# chip-arduino.net
KiCad netlist of a schematic drawn in Altium Designer
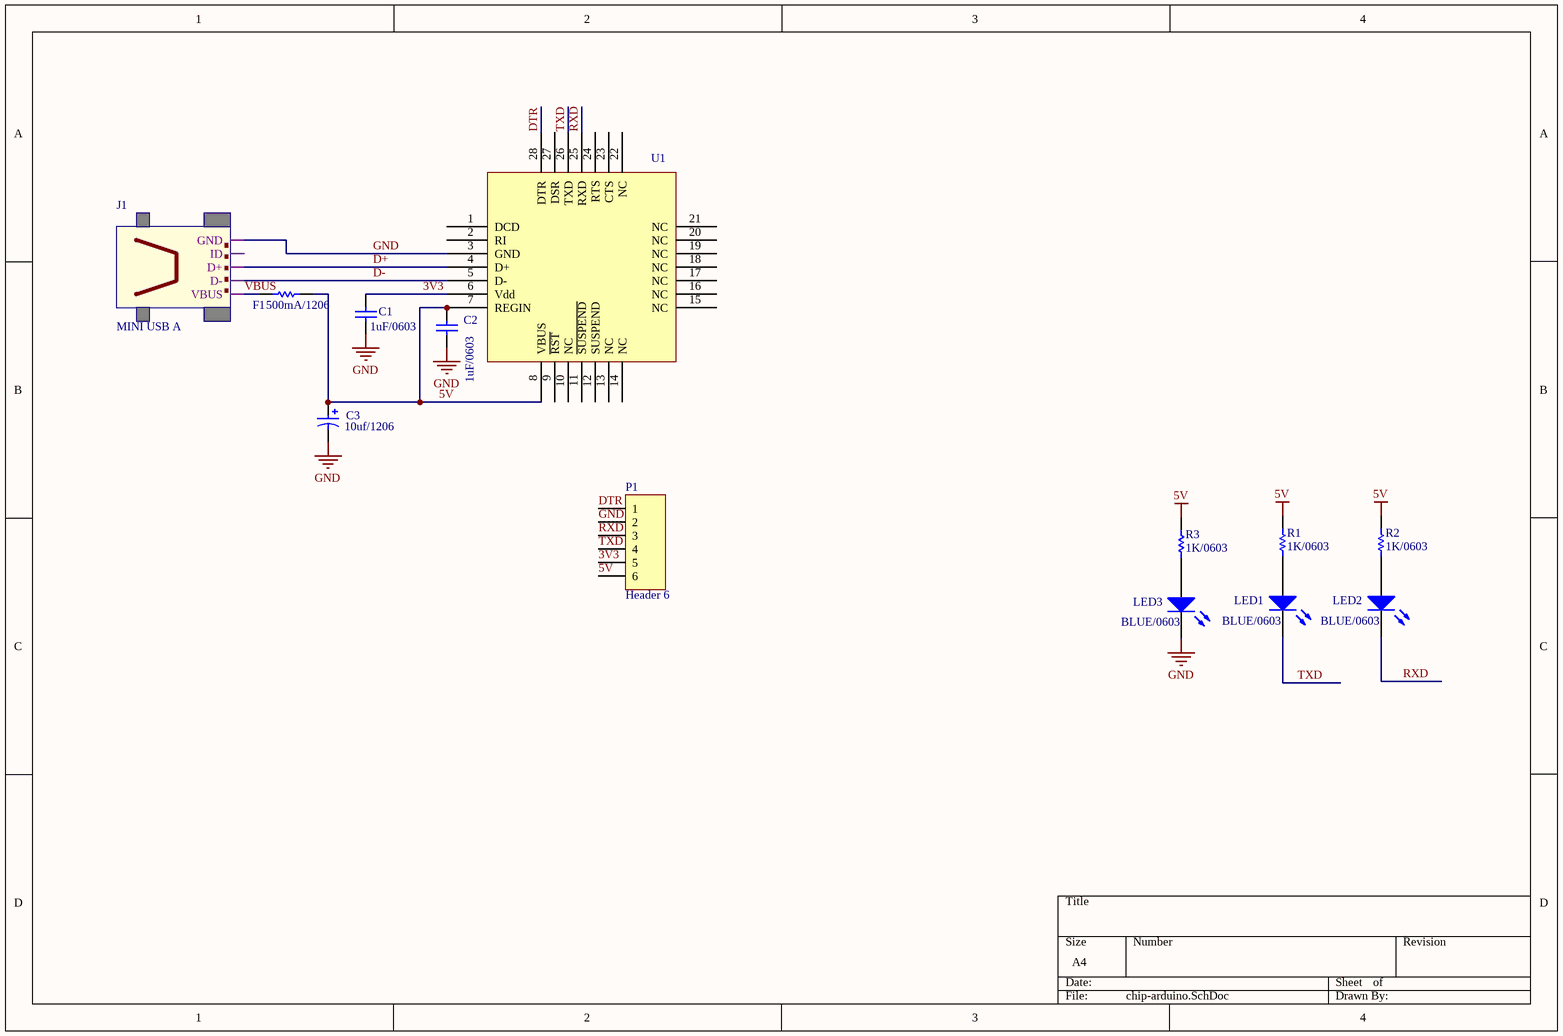
[diagram p0: chip-arduino.SchDoc]

(export (version "E")
  (design (tool "Eeschema 10.0.6"))
  (components
    (comp (ref "C1")
      (value "1uF/0603")
      (footprint "C_0603")
      (description "Capacitor")
      (fields (field (name "PUBLISHER") "Altium Limited"))
      (libsource (lib "Miscellaneous Devices") (part "Cap"))
    )
    (comp (ref "C2")
      (value "1uF/0603")
      (footprint "C_0603")
      (description "Capacitor")
      (fields (field (name "PUBLISHER") "Altium Limited"))
      (libsource (lib "Miscellaneous Devices") (part "Cap"))
    )
    (comp (ref "C3")
      (value "10uf/1206")
      (footprint "C_1206")
      (description "Bi-Polar Capacitor")
      (fields (field (name "Comment") "10uF/10V"))
      (libsource (lib "*") (part "CAP2"))
    )
    (comp (ref "F1")
      (value "500mA/1206")
      (footprint "F_1206")
      (description "Resistor")
      (fields (field (name "PUBLISHER") "Altium Limited"))
      (libsource (lib "Miscellaneous Devices") (part "Res1"))
    )
    (comp (ref "J1")
      (value "MINI USB A")
      (footprint "MICRO USB DIP")
      (libsource (lib "Schlib1") (part "MINI USB A"))
    )
    (comp (ref "LED1")
      (value "BLUE/0603")
      (footprint "LED_0603")
      (description "Typical RED, GREEN, YELLOW, AMBER GaAs LED")
      (fields (field (name "PUBLISHER") "Altium Limited"))
      (libsource (lib "Miscellaneous Devices") (part "LED2"))
    )
    (comp (ref "LED2")
      (value "BLUE/0603")
      (footprint "LED_0603")
      (description "Typical RED, GREEN, YELLOW, AMBER GaAs LED")
      (fields (field (name "PUBLISHER") "Altium Limited"))
      (libsource (lib "Miscellaneous Devices") (part "LED2"))
    )
    (comp (ref "LED3")
      (value "BLUE/0603")
      (footprint "LED_0603")
      (description "Typical RED, GREEN, YELLOW, AMBER GaAs LED")
      (fields (field (name "PUBLISHER") "Altium Limited"))
      (libsource (lib "Miscellaneous Devices") (part "LED2"))
    )
    (comp (ref "P1")
      (value "Header 6")
      (footprint "HDR1X6")
      (description "Header, 6-Pin")
      (fields (field (name "PUBLISHER") "Altium Limited"))
      (libsource (lib "Miscellaneous Connectors") (part "Header 6"))
    )
    (comp (ref "R1")
      (value "1K/0603")
      (footprint "R_0603")
      (description "Resistor")
      (fields (field (name "PUBLISHER") "Altium Limited"))
      (libsource (lib "Miscellaneous Devices") (part "Res1"))
    )
    (comp (ref "R2")
      (value "1K/0603")
      (footprint "R_0603")
      (description "Resistor")
      (fields (field (name "PUBLISHER") "Altium Limited"))
      (libsource (lib "Miscellaneous Devices") (part "Res1"))
    )
    (comp (ref "R3")
      (value "1K/0603")
      (footprint "R_0603")
      (description "Resistor")
      (fields (field (name "PUBLISHER") "Altium Limited"))
      (libsource (lib "Miscellaneous Devices") (part "Res1"))
    )
    (comp (ref "U1")
      (value "CP2102")
      (footprint "CP2102 QFN")
      (libsource (lib "CP2102_SCH") (part "Component_1"))
    )
  )
  (nets
    (net (code "1") (name "/3V3") (class "Default")
      (node (ref "C1") (pin "2") (pinfunction "2_2") (pintype "passive"))
      (node (ref "P1") (pin "5") (pinfunction "5_5") (pintype "passive"))
      (node (ref "U1") (pin "6") (pinfunction "Vdd_6") (pintype "passive"))
    )
    (net (code "2") (name "/D+") (class "Default")
      (node (ref "J1") (pin "D+") (pinfunction "D+_D+") (pintype "passive"))
      (node (ref "U1") (pin "4") (pinfunction "D+_4") (pintype "passive"))
    )
    (net (code "3") (name "/D-") (class "Default")
      (node (ref "J1") (pin "D-") (pinfunction "D-_D-") (pintype "passive"))
      (node (ref "U1") (pin "5") (pinfunction "D-_5") (pintype "passive"))
    )
    (net (code "4") (name "/DTR") (class "Default")
      (node (ref "P1") (pin "1") (pinfunction "1_1") (pintype "passive"))
      (node (ref "U1") (pin "28") (pinfunction "DTR_28") (pintype "passive"))
    )
    (net (code "5") (name "/RXD") (class "Default")
      (node (ref "LED2") (pin "2") (pinfunction "K_2") (pintype "passive"))
      (node (ref "P1") (pin "3") (pinfunction "3_3") (pintype "passive"))
      (node (ref "U1") (pin "25") (pinfunction "RXD_25") (pintype "passive"))
    )
    (net (code "6") (name "/TXD") (class "Default")
      (node (ref "LED1") (pin "2") (pinfunction "K_2") (pintype "passive"))
      (node (ref "P1") (pin "4") (pinfunction "4_4") (pintype "passive"))
      (node (ref "U1") (pin "26") (pinfunction "TXD_26") (pintype "passive"))
    )
    (net (code "7") (name "/VBUS") (class "Default")
      (node (ref "F1") (pin "2") (pinfunction "2_2") (pintype "passive"))
      (node (ref "J1") (pin "VBUS") (pinfunction "VBUS_VBUS") (pintype "passive"))
    )
    (net (code "8") (name "5V") (class "Default")
      (node (ref "C2") (pin "2") (pinfunction "2_2") (pintype "passive"))
      (node (ref "C3") (pin "1") (pinfunction "1_1") (pintype "passive"))
      (node (ref "F1") (pin "1") (pinfunction "1_1") (pintype "passive"))
      (node (ref "P1") (pin "6") (pinfunction "6_6") (pintype "passive"))
      (node (ref "R1") (pin "2") (pinfunction "2_2") (pintype "passive"))
      (node (ref "R2") (pin "2") (pinfunction "2_2") (pintype "passive"))
      (node (ref "R3") (pin "2") (pinfunction "2_2") (pintype "passive"))
      (node (ref "U1") (pin "7") (pinfunction "REGIN_7") (pintype "passive"))
      (node (ref "U1") (pin "8") (pinfunction "VBUS_8") (pintype "passive"))
    )
    (net (code "9") (name "GND") (class "Default")
      (node (ref "C1") (pin "1") (pinfunction "1_1") (pintype "passive"))
      (node (ref "C2") (pin "1") (pinfunction "1_1") (pintype "passive"))
      (node (ref "C3") (pin "2") (pinfunction "2_2") (pintype "passive"))
      (node (ref "J1") (pin "GND") (pinfunction "GND_GND") (pintype "passive"))
      (node (ref "LED3") (pin "2") (pinfunction "K_2") (pintype "passive"))
      (node (ref "P1") (pin "2") (pinfunction "2_2") (pintype "passive"))
      (node (ref "U1") (pin "3") (pinfunction "GND_3") (pintype "passive"))
    )
    (net (code "10") (name "Net-(LED1-A)") (class "Default")
      (node (ref "LED1") (pin "1") (pinfunction "A_1") (pintype "passive"))
      (node (ref "R1") (pin "1") (pinfunction "1_1") (pintype "passive"))
    )
    (net (code "11") (name "Net-(LED2-A)") (class "Default")
      (node (ref "LED2") (pin "1") (pinfunction "A_1") (pintype "passive"))
      (node (ref "R2") (pin "1") (pinfunction "1_1") (pintype "passive"))
    )
    (net (code "12") (name "Net-(LED3-A)") (class "Default")
      (node (ref "LED3") (pin "1") (pinfunction "A_1") (pintype "passive"))
      (node (ref "R3") (pin "1") (pinfunction "1_1") (pintype "passive"))
    )
    (net (code "13") (name "unconnected-(J1-PadID)") (class "Default")
      (node (ref "J1") (pin "ID") (pinfunction "ID_ID") (pintype "passive"))
    )
    (net (code "14") (name "unconnected-(U1-CTS-Pad23)") (class "Default")
      (node (ref "U1") (pin "23") (pinfunction "CTS_23") (pintype "passive"))
    )
    (net (code "15") (name "unconnected-(U1-DCD-Pad1)") (class "Default")
      (node (ref "U1") (pin "1") (pinfunction "DCD_1") (pintype "passive"))
    )
    (net (code "16") (name "unconnected-(U1-DSR-Pad27)") (class "Default")
      (node (ref "U1") (pin "27") (pinfunction "DSR_27") (pintype "passive"))
    )
    (net (code "17") (name "unconnected-(U1-NC-Pad10)") (class "Default")
      (node (ref "U1") (pin "10") (pinfunction "NC_10") (pintype "passive"))
    )
    (net (code "18") (name "unconnected-(U1-NC-Pad13)") (class "Default")
      (node (ref "U1") (pin "13") (pinfunction "NC_13") (pintype "passive"))
    )
    (net (code "19") (name "unconnected-(U1-NC-Pad14)") (class "Default")
      (node (ref "U1") (pin "14") (pinfunction "NC_14") (pintype "passive"))
    )
    (net (code "20") (name "unconnected-(U1-NC-Pad15)") (class "Default")
      (node (ref "U1") (pin "15") (pinfunction "NC_15") (pintype "passive"))
    )
    (net (code "21") (name "unconnected-(U1-NC-Pad16)") (class "Default")
      (node (ref "U1") (pin "16") (pinfunction "NC_16") (pintype "passive"))
    )
    (net (code "22") (name "unconnected-(U1-NC-Pad17)") (class "Default")
      (node (ref "U1") (pin "17") (pinfunction "NC_17") (pintype "passive"))
    )
    (net (code "23") (name "unconnected-(U1-NC-Pad18)") (class "Default")
      (node (ref "U1") (pin "18") (pinfunction "NC_18") (pintype "passive"))
    )
    (net (code "24") (name "unconnected-(U1-NC-Pad19)") (class "Default")
      (node (ref "U1") (pin "19") (pinfunction "NC_19") (pintype "passive"))
    )
    (net (code "25") (name "unconnected-(U1-NC-Pad20)") (class "Default")
      (node (ref "U1") (pin "20") (pinfunction "NC_20") (pintype "passive"))
    )
    (net (code "26") (name "unconnected-(U1-NC-Pad21)") (class "Default")
      (node (ref "U1") (pin "21") (pinfunction "NC_21") (pintype "passive"))
    )
    (net (code "27") (name "unconnected-(U1-NC-Pad22)") (class "Default")
      (node (ref "U1") (pin "22") (pinfunction "NC_22") (pintype "passive"))
    )
    (net (code "28") (name "unconnected-(U1-RI-Pad2)") (class "Default")
      (node (ref "U1") (pin "2") (pinfunction "RI_2") (pintype "passive"))
    )
    (net (code "29") (name "unconnected-(U1-RTS-Pad24)") (class "Default")
      (node (ref "U1") (pin "24") (pinfunction "RTS_24") (pintype "passive"))
    )
    (net (code "30") (name "unconnected-(U1-SUSPEND-Pad12)") (class "Default")
      (node (ref "U1") (pin "12") (pinfunction "SUSPEND_12") (pintype "passive"))
    )
    (net (code "31") (name "unconnected-(U1-~{RST}-Pad9)") (class "Default")
      (node (ref "U1") (pin "9") (pinfunction "~{RST}_9") (pintype "passive"))
    )
    (net (code "32") (name "unconnected-(U1-~{SUSPEND}-Pad11)") (class "Default")
      (node (ref "U1") (pin "11") (pinfunction "~{SUSPEND}_11") (pintype "passive"))
    )
  )
)
